# ALU_Ctrl.net
KiCad netlist of a schematic drawn in Altium Designer
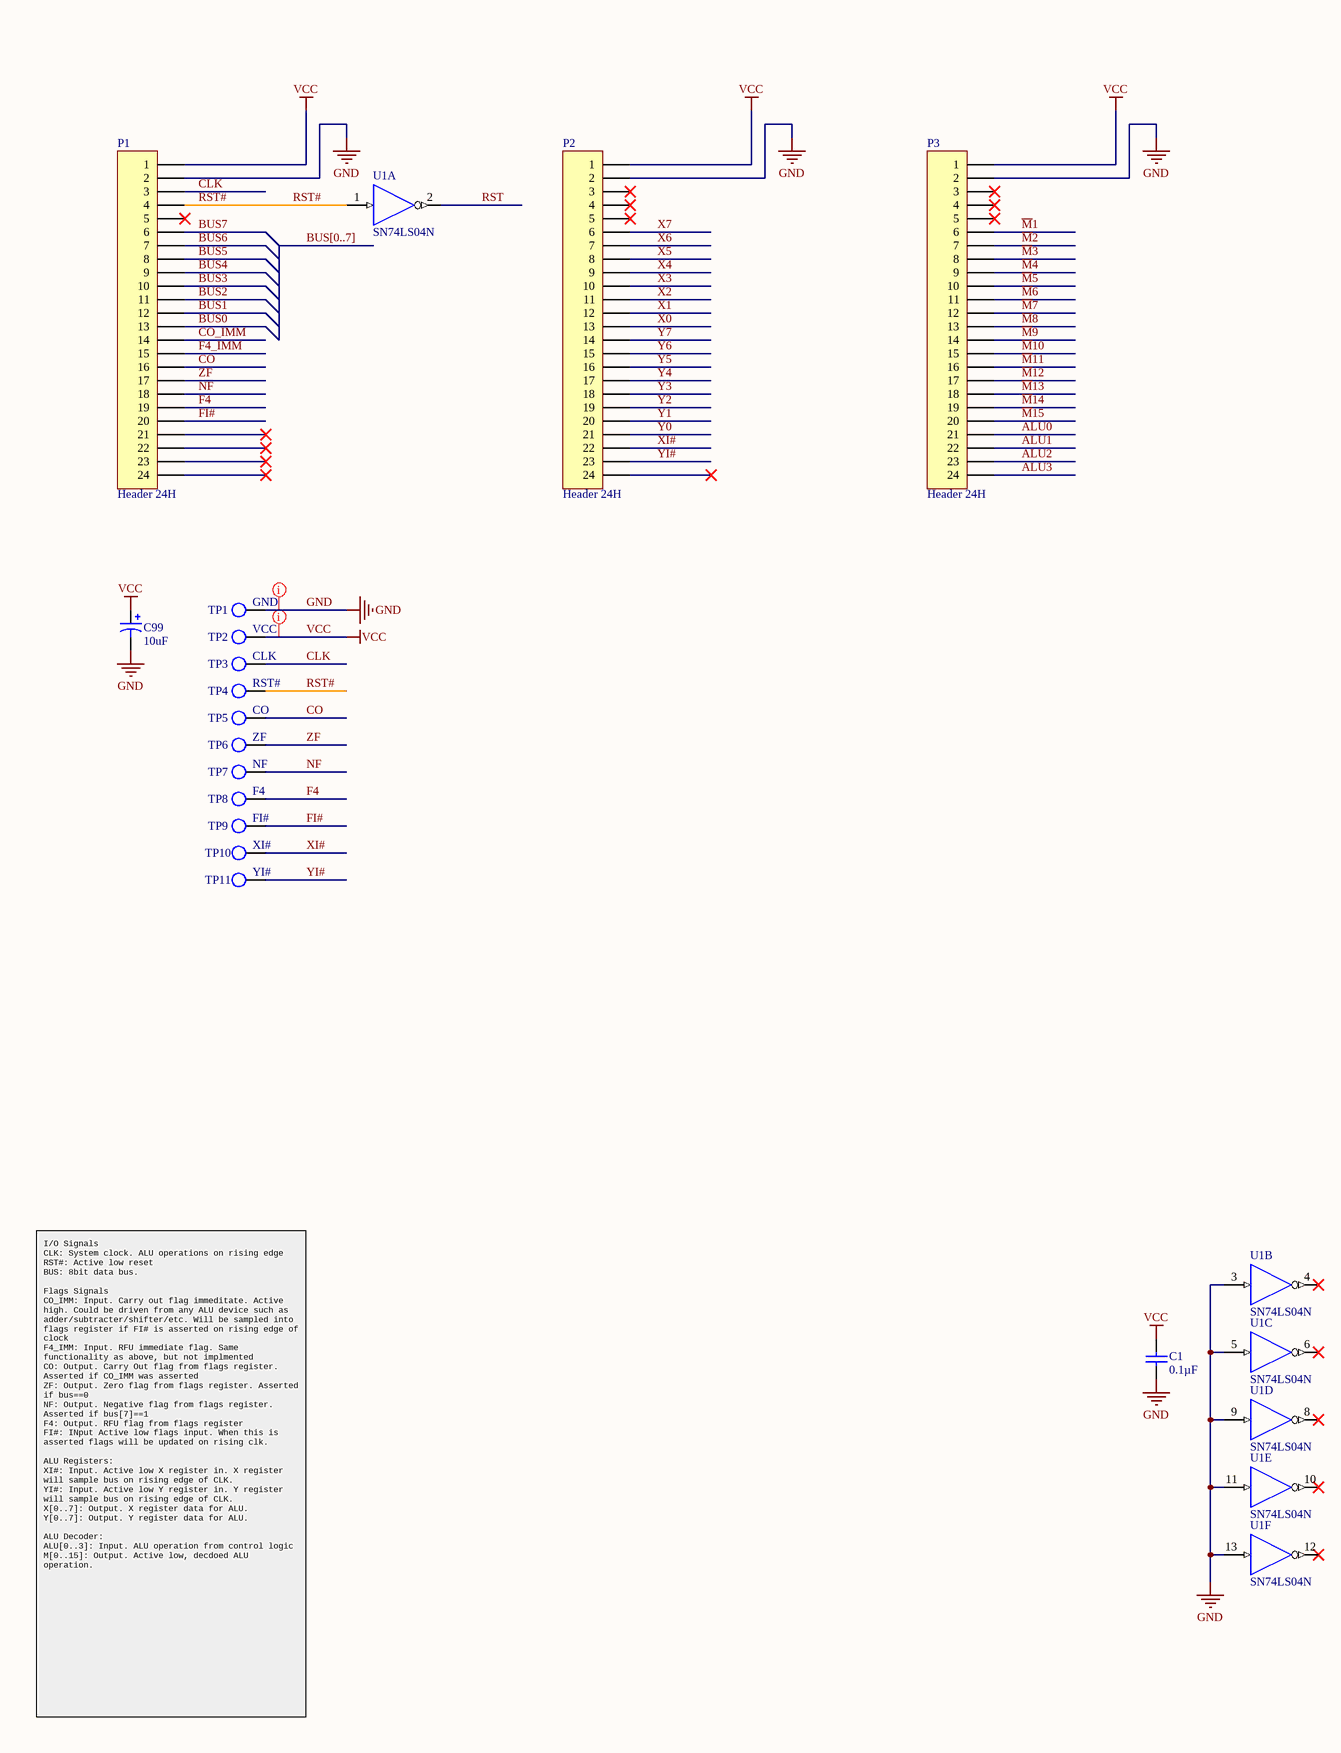
[diagram p0: ALU_Ctrl.SchDoc, left]
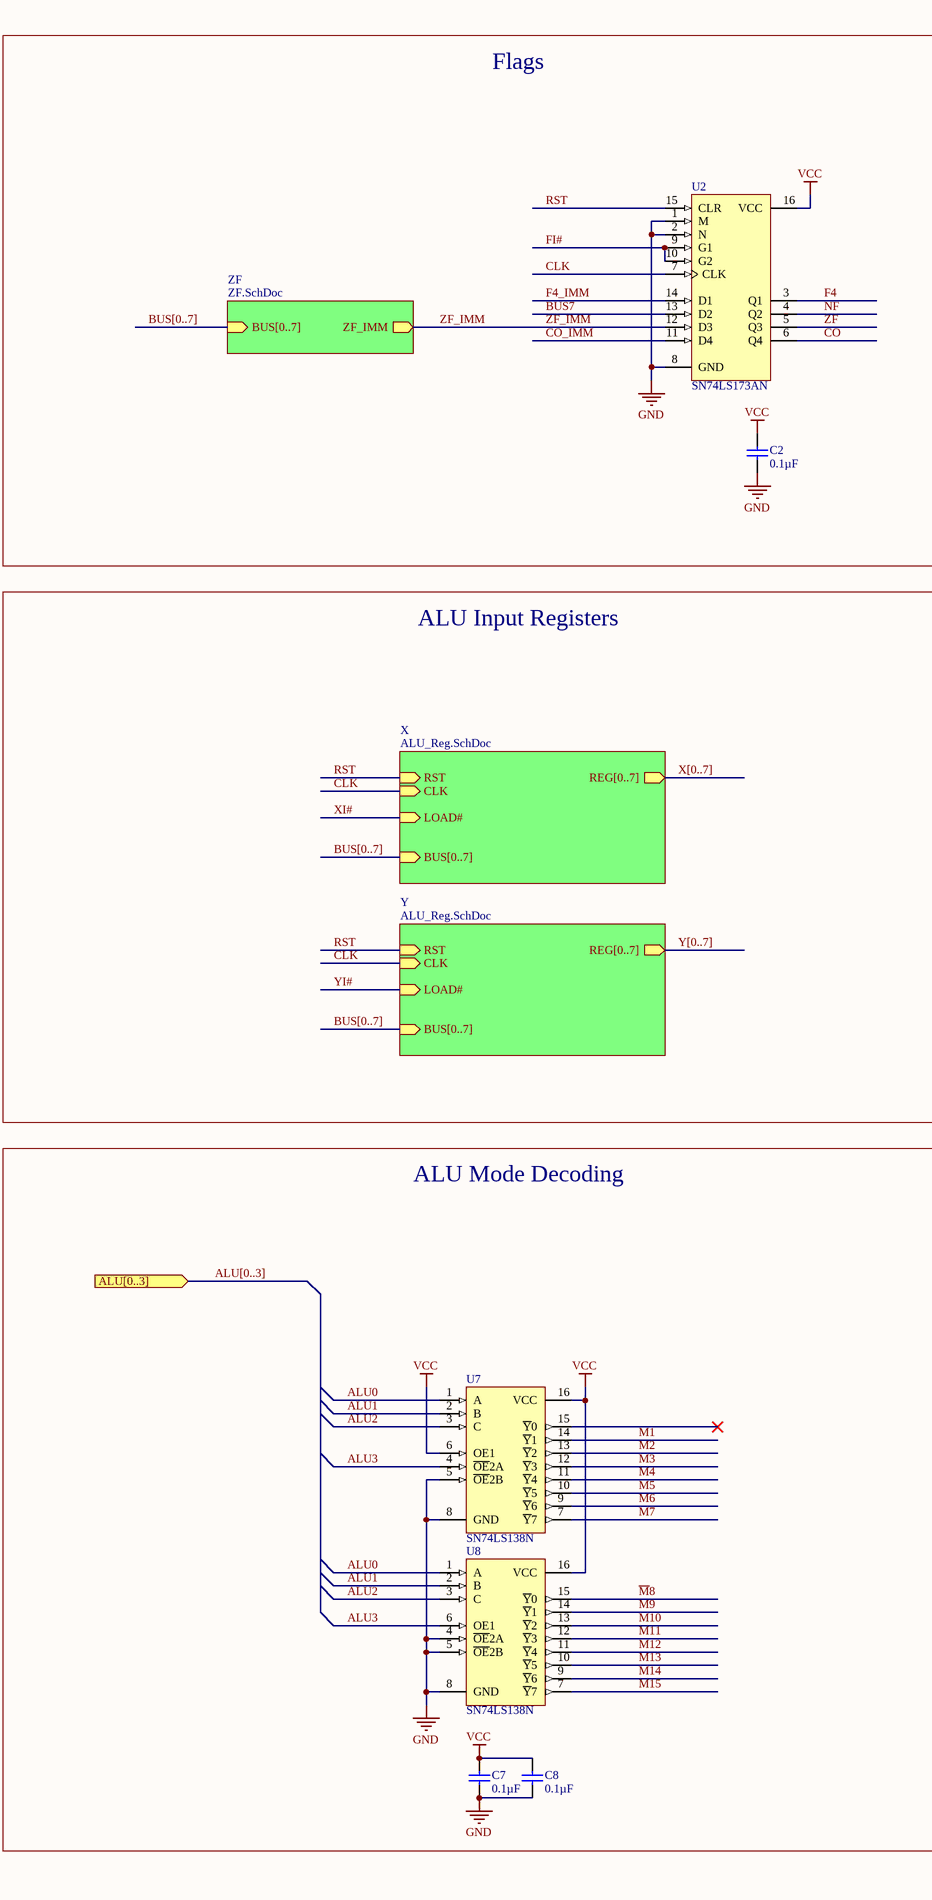
[diagram p1: ALU_Ctrl.SchDoc, right]

(export (version "E")
  (design (tool "Eeschema 10.0.6"))
  (components
    (comp (ref "C1")
      (value "K104K15X7RF5TL2")
      (footprint "VISH-K104K15X7RF5TL2")
      (description "Ceramic Capacitor, 100 nF, +/- 10%, 50 V, -55 to 125 degC, 2-Pin THD, RoHS, Tape and Reel")
      (fields
        (field (name "MANUFACTURER") "Vishay")
        (field (name "TOLERANCE") "±10%")
        (field (name "CAPACITANCE") "0.1µF")
      )
      (libsource (lib "Altium Content Vault") (part "CAP-NP-2"))
    )
    (comp (ref "C2")
      (value "K104K15X7RF5TL2")
      (footprint "VISH-K104K15X7RF5TL2")
      (description "Ceramic Capacitor, 100 nF, +/- 10%, 50 V, -55 to 125 degC, 2-Pin THD, RoHS, Tape and Reel")
      (fields
        (field (name "MANUFACTURER") "Vishay")
        (field (name "TOLERANCE") "±10%")
        (field (name "CAPACITANCE") "0.1µF")
      )
      (libsource (lib "Altium Content Vault") (part "CAP-NP-2"))
    )
    (comp (ref "C7")
      (value "K104K15X7RF5TL2")
      (footprint "VISH-K104K15X7RF5TL2")
      (description "Ceramic Capacitor, 100 nF, +/- 10%, 50 V, -55 to 125 degC, 2-Pin THD, RoHS, Tape and Reel")
      (fields
        (field (name "MANUFACTURER") "Vishay")
        (field (name "TOLERANCE") "±10%")
        (field (name "CAPACITANCE") "0.1µF")
      )
      (libsource (lib "Altium Content Vault") (part "CAP-NP-2"))
    )
    (comp (ref "C8")
      (value "K104K15X7RF5TL2")
      (footprint "VISH-K104K15X7RF5TL2")
      (description "Ceramic Capacitor, 100 nF, +/- 10%, 50 V, -55 to 125 degC, 2-Pin THD, RoHS, Tape and Reel")
      (fields
        (field (name "MANUFACTURER") "Vishay")
        (field (name "TOLERANCE") "±10%")
        (field (name "CAPACITANCE") "0.1µF")
      )
      (libsource (lib "Altium Content Vault") (part "CAP-NP-2"))
    )
    (comp (ref "C99")
      (value "10uF")
      (footprint "C5x7")
      (description "Polarized Capacitor")
      (fields (field (name "Comment") "Cap Pol5") (field (name "PUBLISHER") "Altium Limited"))
      (libsource (lib "Miscellaneous Devices") (part "Cap Pol5"))
    )
    (comp (ref "P1")
      (value "Header 24H")
      (footprint "HDR1X24H")
      (description "Header, 24-Pin, Right Angle")
      (fields (field (name "PUBLISHER") "Altium Limited"))
      (libsource (lib "Miscellaneous Connectors") (part "Header 24H"))
    )
    (comp (ref "P2")
      (value "Header 24H")
      (footprint "HDR1X24H")
      (description "Header, 24-Pin, Right Angle")
      (fields (field (name "PUBLISHER") "Altium Limited"))
      (libsource (lib "Miscellaneous Connectors") (part "Header 24H"))
    )
    (comp (ref "P3")
      (value "Header 24H")
      (footprint "HDR1X24H")
      (description "Header, 24-Pin, Right Angle")
      (fields (field (name "PUBLISHER") "Altium Limited"))
      (libsource (lib "Miscellaneous Connectors") (part "Header 24H"))
    )
    (comp (ref "TP1") (value "GND") (footprint "KSTN-5011_V") (libsource (lib "TP") (part "TP")))
    (comp (ref "TP2") (value "VCC") (footprint "KSTN-5011_V") (libsource (lib "TP") (part "TP")))
    (comp (ref "TP3") (value "CLK") (footprint "KSTN-5011_V") (libsource (lib "TP") (part "TP")))
    (comp (ref "TP4") (value "RST#") (footprint "KSTN-5011_V") (libsource (lib "TP") (part "TP")))
    (comp (ref "TP5") (value "CO") (footprint "KSTN-5011_V") (libsource (lib "TP") (part "TP")))
    (comp (ref "TP6") (value "ZF") (footprint "KSTN-5011_V") (libsource (lib "TP") (part "TP")))
    (comp (ref "TP7") (value "NF") (footprint "KSTN-5011_V") (libsource (lib "TP") (part "TP")))
    (comp (ref "TP8") (value "F4") (footprint "KSTN-5011_V") (libsource (lib "TP") (part "TP")))
    (comp (ref "TP9") (value "FI#") (footprint "KSTN-5011_V") (libsource (lib "TP") (part "TP")))
    (comp (ref "TP10") (value "XI#") (footprint "KSTN-5011_V") (libsource (lib "TP") (part "TP")))
    (comp (ref "TP11") (value "YI#") (footprint "KSTN-5011_V") (libsource (lib "TP") (part "TP")))
    (comp (ref "U1")
      (value "SN74LS04N")
      (footprint "N014")
      (description "Hex Inverter")
      (fields (field (name "PUBLISHER") "Altium Limited"))
      (libsource (lib "TI Logic Gate 2") (part "SN74LS04N"))
    )
    (comp (ref "U2")
      (value "SN74LS173AN")
      (footprint "N016D")
      (description "4-Bit D-Type Register with 3-State Outputs")
      (fields (field (name "PUBLISHER") "Altium Limited"))
      (libsource (lib "TI Logic Flip-Flop") (part "SN74LS173AN"))
    )
    (comp (ref "U7")
      (value "SN74LS138N")
      (footprint "N016")
      (description "3-Line to 8-Line Decoder / Demultiplexer")
      (fields (field (name "PUBLISHER") "Altium Limited"))
      (libsource (lib "TI Logic Decoder Demux") (part "SN74LS138N"))
    )
    (comp (ref "U8")
      (value "SN74LS138N")
      (footprint "N016")
      (description "3-Line to 8-Line Decoder / Demultiplexer")
      (fields (field (name "PUBLISHER") "Altium Limited"))
      (libsource (lib "TI Logic Decoder Demux") (part "SN74LS138N"))
    )
  )
  (nets
    (net (code "1") (name "/ALU0") (class "Default")
      (node (ref "P3") (pin "21") (pinfunction "21_21") (pintype "passive"))
      (node (ref "U7") (pin "1") (pinfunction "A_1") (pintype "input"))
      (node (ref "U8") (pin "1") (pinfunction "A_1") (pintype "input"))
    )
    (net (code "2") (name "/ALU1") (class "Default")
      (node (ref "P3") (pin "22") (pinfunction "22_22") (pintype "passive"))
      (node (ref "U7") (pin "2") (pinfunction "B_2") (pintype "input"))
      (node (ref "U8") (pin "2") (pinfunction "B_2") (pintype "input"))
    )
    (net (code "3") (name "/ALU2") (class "Default")
      (node (ref "P3") (pin "23") (pinfunction "23_23") (pintype "passive"))
      (node (ref "U7") (pin "3") (pinfunction "C_3") (pintype "input"))
      (node (ref "U8") (pin "3") (pinfunction "C_3") (pintype "input"))
    )
    (net (code "4") (name "/ALU3") (class "Default")
      (node (ref "P3") (pin "24") (pinfunction "24_24") (pintype "passive"))
      (node (ref "U7") (pin "4") (pinfunction "~{OE}2A_4") (pintype "input"))
      (node (ref "U8") (pin "6") (pinfunction "OE1_6") (pintype "input"))
    )
    (net (code "6") (name "/BUS0") (class "Default")
      (node (ref "P1") (pin "13") (pinfunction "13_13") (pintype "passive"))
    )
    (net (code "7") (name "/BUS1") (class "Default")
      (node (ref "P1") (pin "12") (pinfunction "12_12") (pintype "passive"))
    )
    (net (code "8") (name "/BUS2") (class "Default")
      (node (ref "P1") (pin "11") (pinfunction "11_11") (pintype "passive"))
    )
    (net (code "9") (name "/BUS3") (class "Default")
      (node (ref "P1") (pin "10") (pinfunction "10_10") (pintype "passive"))
    )
    (net (code "10") (name "/BUS4") (class "Default")
      (node (ref "P1") (pin "9") (pinfunction "9_9") (pintype "passive"))
    )
    (net (code "11") (name "/BUS5") (class "Default")
      (node (ref "P1") (pin "8") (pinfunction "8_8") (pintype "passive"))
    )
    (net (code "12") (name "/BUS6") (class "Default")
      (node (ref "P1") (pin "7") (pinfunction "7_7") (pintype "passive"))
    )
    (net (code "13") (name "/BUS7") (class "Default")
      (node (ref "P1") (pin "6") (pinfunction "6_6") (pintype "passive"))
      (node (ref "U2") (pin "13") (pinfunction "D2_13") (pintype "input"))
    )
    (net (code "15") (name "/CLK") (class "Default")
      (node (ref "P1") (pin "3") (pinfunction "3_3") (pintype "passive"))
      (node (ref "TP3") (pin "1") (pintype "passive"))
      (node (ref "U2") (pin "7") (pinfunction "CLK_7") (pintype "input"))
    )
    (net (code "16") (name "/CO") (class "Default")
      (node (ref "P1") (pin "16") (pinfunction "16_16") (pintype "passive"))
      (node (ref "TP5") (pin "1") (pintype "passive"))
      (node (ref "U2") (pin "6") (pinfunction "Q4_6") (pintype "tri_state"))
    )
    (net (code "17") (name "/CO_IMM") (class "Default")
      (node (ref "P1") (pin "14") (pinfunction "14_14") (pintype "passive"))
      (node (ref "U2") (pin "11") (pinfunction "D4_11") (pintype "input"))
    )
    (net (code "18") (name "/F4") (class "Default")
      (node (ref "P1") (pin "19") (pinfunction "19_19") (pintype "passive"))
      (node (ref "TP8") (pin "1") (pintype "passive"))
      (node (ref "U2") (pin "3") (pinfunction "Q1_3") (pintype "tri_state"))
    )
    (net (code "19") (name "/F4_IMM") (class "Default")
      (node (ref "P1") (pin "15") (pinfunction "15_15") (pintype "passive"))
      (node (ref "U2") (pin "14") (pinfunction "D1_14") (pintype "input"))
    )
    (net (code "20") (name "/FI#") (class "Default")
      (node (ref "P1") (pin "20") (pinfunction "20_20") (pintype "passive"))
      (node (ref "TP9") (pin "1") (pintype "passive"))
      (node (ref "U2") (pin "10") (pinfunction "G2_10") (pintype "input"))
      (node (ref "U2") (pin "9") (pinfunction "G1_9") (pintype "input"))
    )
    (net (code "21") (name "/NF") (class "Default")
      (node (ref "P1") (pin "18") (pinfunction "18_18") (pintype "passive"))
      (node (ref "TP7") (pin "1") (pintype "passive"))
      (node (ref "U2") (pin "4") (pinfunction "Q2_4") (pintype "tri_state"))
    )
    (net (code "22") (name "/RST") (class "Default")
      (node (ref "U1") (pin "2") (pinfunction "Y_2") (pintype "output"))
      (node (ref "U2") (pin "15") (pinfunction "CLR_15") (pintype "input"))
    )
    (net (code "23") (name "/RST#") (class "Default")
      (node (ref "P1") (pin "4") (pinfunction "4_4") (pintype "passive"))
      (node (ref "TP4") (pin "1") (pintype "passive"))
      (node (ref "U1") (pin "1") (pinfunction "A_1") (pintype "input"))
    )
    (net (code "24") (name "/X0") (class "Default")
      (node (ref "P2") (pin "13") (pinfunction "13_13") (pintype "passive"))
    )
    (net (code "25") (name "/X1") (class "Default")
      (node (ref "P2") (pin "12") (pinfunction "12_12") (pintype "passive"))
    )
    (net (code "26") (name "/X2") (class "Default")
      (node (ref "P2") (pin "11") (pinfunction "11_11") (pintype "passive"))
    )
    (net (code "27") (name "/X3") (class "Default")
      (node (ref "P2") (pin "10") (pinfunction "10_10") (pintype "passive"))
    )
    (net (code "28") (name "/X4") (class "Default")
      (node (ref "P2") (pin "9") (pinfunction "9_9") (pintype "passive"))
    )
    (net (code "29") (name "/X5") (class "Default")
      (node (ref "P2") (pin "8") (pinfunction "8_8") (pintype "passive"))
    )
    (net (code "30") (name "/X6") (class "Default")
      (node (ref "P2") (pin "7") (pinfunction "7_7") (pintype "passive"))
    )
    (net (code "31") (name "/X7") (class "Default")
      (node (ref "P2") (pin "6") (pinfunction "6_6") (pintype "passive"))
    )
    (net (code "32") (name "/XI#") (class "Default")
      (node (ref "P2") (pin "22") (pinfunction "22_22") (pintype "passive"))
      (node (ref "TP10") (pin "1") (pintype "passive"))
    )
    (net (code "34") (name "/Y0") (class "Default")
      (node (ref "P2") (pin "21") (pinfunction "21_21") (pintype "passive"))
    )
    (net (code "35") (name "/Y1") (class "Default")
      (node (ref "P2") (pin "20") (pinfunction "20_20") (pintype "passive"))
    )
    (net (code "36") (name "/Y2") (class "Default")
      (node (ref "P2") (pin "19") (pinfunction "19_19") (pintype "passive"))
    )
    (net (code "37") (name "/Y3") (class "Default")
      (node (ref "P2") (pin "18") (pinfunction "18_18") (pintype "passive"))
    )
    (net (code "38") (name "/Y4") (class "Default")
      (node (ref "P2") (pin "17") (pinfunction "17_17") (pintype "passive"))
    )
    (net (code "39") (name "/Y5") (class "Default")
      (node (ref "P2") (pin "16") (pinfunction "16_16") (pintype "passive"))
    )
    (net (code "40") (name "/Y6") (class "Default")
      (node (ref "P2") (pin "15") (pinfunction "15_15") (pintype "passive"))
    )
    (net (code "41") (name "/Y7") (class "Default")
      (node (ref "P2") (pin "14") (pinfunction "14_14") (pintype "passive"))
    )
    (net (code "42") (name "/YI#") (class "Default")
      (node (ref "P2") (pin "23") (pinfunction "23_23") (pintype "passive"))
      (node (ref "TP11") (pin "1") (pintype "passive"))
    )
    (net (code "44") (name "/ZF") (class "Default")
      (node (ref "P1") (pin "17") (pinfunction "17_17") (pintype "passive"))
      (node (ref "TP6") (pin "1") (pintype "passive"))
      (node (ref "U2") (pin "5") (pinfunction "Q3_5") (pintype "tri_state"))
    )
    (net (code "45") (name "/ZF_IMM") (class "Default")
      (node (ref "U2") (pin "12") (pinfunction "D3_12") (pintype "input"))
    )
    (net (code "46") (name "/~{M}1") (class "Default")
      (node (ref "P3") (pin "6") (pinfunction "6_6") (pintype "passive"))
      (node (ref "U7") (pin "14") (pinfunction "~{Y}1_14") (pintype "output"))
    )
    (net (code "47") (name "/~{M}2") (class "Default")
      (node (ref "P3") (pin "7") (pinfunction "7_7") (pintype "passive"))
      (node (ref "U7") (pin "13") (pinfunction "~{Y}2_13") (pintype "output"))
    )
    (net (code "48") (name "/~{M}3") (class "Default")
      (node (ref "P3") (pin "8") (pinfunction "8_8") (pintype "passive"))
      (node (ref "U7") (pin "12") (pinfunction "~{Y}3_12") (pintype "output"))
    )
    (net (code "49") (name "/~{M}4") (class "Default")
      (node (ref "P3") (pin "9") (pinfunction "9_9") (pintype "passive"))
      (node (ref "U7") (pin "11") (pinfunction "~{Y}4_11") (pintype "output"))
    )
    (net (code "50") (name "/~{M}5") (class "Default")
      (node (ref "P3") (pin "10") (pinfunction "10_10") (pintype "passive"))
      (node (ref "U7") (pin "10") (pinfunction "~{Y}5_10") (pintype "output"))
    )
    (net (code "51") (name "/~{M}6") (class "Default")
      (node (ref "P3") (pin "11") (pinfunction "11_11") (pintype "passive"))
      (node (ref "U7") (pin "9") (pinfunction "~{Y}6_9") (pintype "output"))
    )
    (net (code "52") (name "/~{M}7") (class "Default")
      (node (ref "P3") (pin "12") (pinfunction "12_12") (pintype "passive"))
      (node (ref "U7") (pin "7") (pinfunction "~{Y}7_7") (pintype "output"))
    )
    (net (code "53") (name "/~{M}8") (class "Default")
      (node (ref "P3") (pin "13") (pinfunction "13_13") (pintype "passive"))
      (node (ref "U8") (pin "15") (pinfunction "~{Y}0_15") (pintype "output"))
    )
    (net (code "54") (name "/~{M}9") (class "Default")
      (node (ref "P3") (pin "14") (pinfunction "14_14") (pintype "passive"))
      (node (ref "U8") (pin "14") (pinfunction "~{Y}1_14") (pintype "output"))
    )
    (net (code "55") (name "/~{M}10") (class "Default")
      (node (ref "P3") (pin "15") (pinfunction "15_15") (pintype "passive"))
      (node (ref "U8") (pin "13") (pinfunction "~{Y}2_13") (pintype "output"))
    )
    (net (code "56") (name "/~{M}11") (class "Default")
      (node (ref "P3") (pin "16") (pinfunction "16_16") (pintype "passive"))
      (node (ref "U8") (pin "12") (pinfunction "~{Y}3_12") (pintype "output"))
    )
    (net (code "57") (name "/~{M}12") (class "Default")
      (node (ref "P3") (pin "17") (pinfunction "17_17") (pintype "passive"))
      (node (ref "U8") (pin "11") (pinfunction "~{Y}4_11") (pintype "output"))
    )
    (net (code "58") (name "/~{M}13") (class "Default")
      (node (ref "P3") (pin "18") (pinfunction "18_18") (pintype "passive"))
      (node (ref "U8") (pin "10") (pinfunction "~{Y}5_10") (pintype "output"))
    )
    (net (code "59") (name "/~{M}14") (class "Default")
      (node (ref "P3") (pin "19") (pinfunction "19_19") (pintype "passive"))
      (node (ref "U8") (pin "9") (pinfunction "~{Y}6_9") (pintype "output"))
    )
    (net (code "60") (name "/~{M}15") (class "Default")
      (node (ref "P3") (pin "20") (pinfunction "20_20") (pintype "passive"))
      (node (ref "U8") (pin "7") (pinfunction "~{Y}7_7") (pintype "output"))
    )
    (net (code "61") (name "GND") (class "Default")
      (node (ref "C1") (pin "2") (pinfunction "2_2") (pintype "passive"))
      (node (ref "C2") (pin "2") (pinfunction "2_2") (pintype "passive"))
      (node (ref "C7") (pin "2") (pinfunction "2_2") (pintype "passive"))
      (node (ref "C8") (pin "2") (pinfunction "2_2") (pintype "passive"))
      (node (ref "C99") (pin "2") (pinfunction "2_2") (pintype "passive"))
      (node (ref "P1") (pin "2") (pinfunction "2_2") (pintype "passive"))
      (node (ref "P2") (pin "2") (pinfunction "2_2") (pintype "passive"))
      (node (ref "P3") (pin "2") (pinfunction "2_2") (pintype "passive"))
      (node (ref "TP1") (pin "1") (pintype "passive"))
      (node (ref "U1") (pin "11") (pinfunction "A_11") (pintype "input"))
      (node (ref "U1") (pin "13") (pinfunction "A_13") (pintype "input"))
      (node (ref "U1") (pin "3") (pinfunction "A_3") (pintype "input"))
      (node (ref "U1") (pin "5") (pinfunction "A_5") (pintype "input"))
      (node (ref "U1") (pin "7") (pinfunction "GND_7") (pintype "power_in"))
      (node (ref "U1") (pin "9") (pinfunction "A_9") (pintype "input"))
      (node (ref "U2") (pin "1") (pinfunction "M_1") (pintype "input"))
      (node (ref "U2") (pin "2") (pinfunction "N_2") (pintype "input"))
      (node (ref "U2") (pin "8") (pinfunction "GND_8") (pintype "power_in"))
      (node (ref "U7") (pin "5") (pinfunction "~{OE}2B_5") (pintype "input"))
      (node (ref "U7") (pin "8") (pinfunction "GND_8") (pintype "power_in"))
      (node (ref "U8") (pin "4") (pinfunction "~{OE}2A_4") (pintype "input"))
      (node (ref "U8") (pin "5") (pinfunction "~{OE}2B_5") (pintype "input"))
      (node (ref "U8") (pin "8") (pinfunction "GND_8") (pintype "power_in"))
    )
    (net (code "62") (name "VCC") (class "Default")
      (node (ref "C1") (pin "1") (pinfunction "1_1") (pintype "passive"))
      (node (ref "C2") (pin "1") (pinfunction "1_1") (pintype "passive"))
      (node (ref "C7") (pin "1") (pinfunction "1_1") (pintype "passive"))
      (node (ref "C8") (pin "1") (pinfunction "1_1") (pintype "passive"))
      (node (ref "C99") (pin "1") (pinfunction "1_1") (pintype "passive"))
      (node (ref "P1") (pin "1") (pinfunction "1_1") (pintype "passive"))
      (node (ref "P2") (pin "1") (pinfunction "1_1") (pintype "passive"))
      (node (ref "P3") (pin "1") (pinfunction "1_1") (pintype "passive"))
      (node (ref "TP2") (pin "1") (pintype "passive"))
      (node (ref "U1") (pin "14") (pinfunction "VCC_14") (pintype "power_in"))
      (node (ref "U2") (pin "16") (pinfunction "VCC_16") (pintype "power_in"))
      (node (ref "U7") (pin "16") (pinfunction "VCC_16") (pintype "power_in"))
      (node (ref "U7") (pin "6") (pinfunction "OE1_6") (pintype "input"))
      (node (ref "U8") (pin "16") (pinfunction "VCC_16") (pintype "power_in"))
    )
    (net (code "63") (name "unconnected-(P1-Pad5)") (class "Default")
      (node (ref "P1") (pin "5") (pinfunction "5_5") (pintype "passive+no_connect"))
    )
    (net (code "64") (name "unconnected-(P1-Pad21)") (class "Default")
      (node (ref "P1") (pin "21") (pinfunction "21_21") (pintype "passive+no_connect"))
    )
    (net (code "65") (name "unconnected-(P1-Pad22)") (class "Default")
      (node (ref "P1") (pin "22") (pinfunction "22_22") (pintype "passive+no_connect"))
    )
    (net (code "66") (name "unconnected-(P1-Pad23)") (class "Default")
      (node (ref "P1") (pin "23") (pinfunction "23_23") (pintype "passive+no_connect"))
    )
    (net (code "67") (name "unconnected-(P1-Pad24)") (class "Default")
      (node (ref "P1") (pin "24") (pinfunction "24_24") (pintype "passive+no_connect"))
    )
    (net (code "68") (name "unconnected-(P2-Pad3)") (class "Default")
      (node (ref "P2") (pin "3") (pinfunction "3_3") (pintype "passive+no_connect"))
    )
    (net (code "69") (name "unconnected-(P2-Pad4)") (class "Default")
      (node (ref "P2") (pin "4") (pinfunction "4_4") (pintype "passive+no_connect"))
    )
    (net (code "70") (name "unconnected-(P2-Pad5)") (class "Default")
      (node (ref "P2") (pin "5") (pinfunction "5_5") (pintype "passive+no_connect"))
    )
    (net (code "71") (name "unconnected-(P2-Pad24)") (class "Default")
      (node (ref "P2") (pin "24") (pinfunction "24_24") (pintype "passive+no_connect"))
    )
    (net (code "72") (name "unconnected-(P3-Pad3)") (class "Default")
      (node (ref "P3") (pin "3") (pinfunction "3_3") (pintype "passive+no_connect"))
    )
    (net (code "73") (name "unconnected-(P3-Pad4)") (class "Default")
      (node (ref "P3") (pin "4") (pinfunction "4_4") (pintype "passive+no_connect"))
    )
    (net (code "74") (name "unconnected-(P3-Pad5)") (class "Default")
      (node (ref "P3") (pin "5") (pinfunction "5_5") (pintype "passive+no_connect"))
    )
    (net (code "75") (name "unconnected-(U1B-Y-Pad4)") (class "Default")
      (node (ref "U1") (pin "4") (pinfunction "Y_4") (pintype "output+no_connect"))
    )
    (net (code "76") (name "unconnected-(U1C-Y-Pad6)") (class "Default")
      (node (ref "U1") (pin "6") (pinfunction "Y_6") (pintype "output+no_connect"))
    )
    (net (code "77") (name "unconnected-(U1D-Y-Pad8)") (class "Default")
      (node (ref "U1") (pin "8") (pinfunction "Y_8") (pintype "output+no_connect"))
    )
    (net (code "78") (name "unconnected-(U1E-Y-Pad10)") (class "Default")
      (node (ref "U1") (pin "10") (pinfunction "Y_10") (pintype "output+no_connect"))
    )
    (net (code "79") (name "unconnected-(U1F-Y-Pad12)") (class "Default")
      (node (ref "U1") (pin "12") (pinfunction "Y_12") (pintype "output+no_connect"))
    )
    (net (code "80") (name "unconnected-(U7-~{Y}0-Pad15)") (class "Default")
      (node (ref "U7") (pin "15") (pinfunction "~{Y}0_15") (pintype "output+no_connect"))
    )
  )
)
